# ValdisMCU.net
KiCad netlist of a schematic drawn in Altium Designer
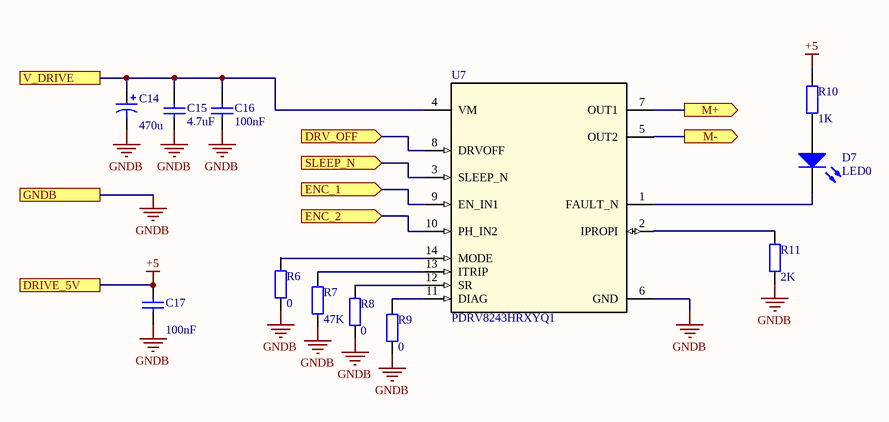
[diagram p0: ValdisMCU.SchDoc]

(export (version "E")
  (design (tool "Eeschema 10.0.6"))
  (components
    (comp (ref "C14")
      (value "470u")
      (footprint "RB7.6-15")
      (description "Polarized Capacitor (Radial)")
      (fields (field (name "Comment") "Cap Pol1") (field (name "PUBLISHER") "Altium Limited"))
      (libsource (lib "Miscellaneous Devices") (part "Cap Pol1"))
    )
    (comp (ref "C15")
      (value "4.7uF")
      (description "Capacitor")
      (libsource (lib "Simulation Generic Components") (part "Capacitor"))
    )
    (comp (ref "C16")
      (value "100nF")
      (description "Capacitor")
      (libsource (lib "Simulation Generic Components") (part "Capacitor"))
    )
    (comp (ref "C17")
      (value "100nF")
      (footprint "RAD-0.3")
      (description "Capacitor")
      (fields (field (name "Comment") "Cap") (field (name "PUBLISHER") "Altium Limited"))
      (libsource (lib "Miscellaneous Devices") (part "Cap"))
    )
    (comp (ref "D7")
      (value "LED0")
      (footprint "LED-0")
      (description "Typical INFRARED GaAs LED")
      (fields (field (name "PUBLISHER") "Altium Limited"))
      (libsource (lib "Miscellaneous Devices") (part "LED0"))
    )
    (comp (ref "R6")
      (value "0")
      (footprint "AXIAL-0.4")
      (description "Resistor")
      (fields (field (name "Comment") "Res2") (field (name "PUBLISHER") "Altium Limited"))
      (libsource (lib "Miscellaneous Devices") (part "Res2"))
    )
    (comp (ref "R7")
      (value "47K")
      (footprint "AXIAL-0.4")
      (description "Resistor")
      (fields (field (name "Comment") "Res2") (field (name "PUBLISHER") "Altium Limited"))
      (libsource (lib "Miscellaneous Devices") (part "Res2"))
    )
    (comp (ref "R8")
      (value "0")
      (footprint "AXIAL-0.4")
      (description "Resistor")
      (fields (field (name "Comment") "Res2") (field (name "PUBLISHER") "Altium Limited"))
      (libsource (lib "") (part "Res2_1"))
    )
    (comp (ref "R9")
      (value "0")
      (footprint "AXIAL-0.4")
      (description "Resistor")
      (fields (field (name "Comment") "Res2") (field (name "PUBLISHER") "Altium Limited"))
      (libsource (lib "Miscellaneous Devices") (part "Res2"))
    )
    (comp (ref "R10")
      (value "1K")
      (footprint "AXIAL-0.4")
      (description "Resistor")
      (fields (field (name "Comment") "Res2") (field (name "PUBLISHER") "Altium Limited"))
      (libsource (lib "Miscellaneous Devices") (part "Res2"))
    )
    (comp (ref "R11")
      (value "2K")
      (footprint "AXIAL-0.4")
      (description "Resistor")
      (fields (field (name "Comment") "Res2") (field (name "PUBLISHER") "Altium Limited"))
      (libsource (lib "Miscellaneous Devices") (part "Res2"))
    )
    (comp (ref "U7")
      (value "PDRV8243HRXYQ1")
      (footprint "RXY0014A-MFG")
      (description "No Description Available")
      (fields (field (name "COPYRIGHT") "Copyright (C) 2022 Ultra Librarian. All rights reserved."))
      (libsource (lib "PDRV8243HRXYQ1") (part "PDRV8243HRXYQ1"))
    )
  )
  (nets
    (net (code "1") (name "+5") (class "Default")
      (node (ref "C17") (pin "2") (pinfunction "2_2") (pintype "passive"))
      (node (ref "R10") (pin "2") (pinfunction "2_2") (pintype "passive"))
    )
    (net (code "2") (name "/DRV_OFF") (class "Default")
      (node (ref "U7") (pin "8") (pinfunction "DRVOFF_8") (pintype "input"))
    )
    (net (code "3") (name "/ENC_1") (class "Default")
      (node (ref "U7") (pin "9") (pinfunction "EN_IN1_9") (pintype "input"))
    )
    (net (code "4") (name "/ENC_2") (class "Default")
      (node (ref "U7") (pin "10") (pinfunction "PH_IN2_10") (pintype "input"))
    )
    (net (code "5") (name "/M+") (class "Default")
      (node (ref "U7") (pin "7") (pinfunction "OUT1_7") (pintype "passive"))
    )
    (net (code "6") (name "/M-") (class "Default")
      (node (ref "U7") (pin "5") (pinfunction "OUT2_5") (pintype "passive"))
    )
    (net (code "7") (name "/SLEEP_N") (class "Default")
      (node (ref "U7") (pin "3") (pinfunction "SLEEP_N_3") (pintype "input"))
    )
    (net (code "8") (name "/V_DRIVE") (class "Default")
      (node (ref "C14") (pin "1") (pinfunction "1_1") (pintype "passive"))
      (node (ref "C15") (pin "2") (pinfunction "2_2") (pintype "passive"))
      (node (ref "C16") (pin "1") (pinfunction "1_1") (pintype "passive"))
      (node (ref "U7") (pin "4") (pinfunction "VM_4") (pintype "power_in"))
    )
    (net (code "9") (name "GNDB") (class "Default")
      (node (ref "C14") (pin "2") (pinfunction "2_2") (pintype "passive"))
      (node (ref "C15") (pin "1") (pinfunction "1_1") (pintype "passive"))
      (node (ref "C16") (pin "2") (pinfunction "2_2") (pintype "passive"))
      (node (ref "C17") (pin "1") (pinfunction "1_1") (pintype "passive"))
      (node (ref "R11") (pin "1") (pinfunction "1_1") (pintype "passive"))
      (node (ref "R6") (pin "1") (pinfunction "1_1") (pintype "passive"))
      (node (ref "R7") (pin "1") (pinfunction "1_1") (pintype "passive"))
      (node (ref "R8") (pin "2") (pinfunction "2_2") (pintype "passive"))
      (node (ref "R9") (pin "1") (pinfunction "1_1") (pintype "passive"))
      (node (ref "U7") (pin "6") (pinfunction "GND_6") (pintype "power_in"))
    )
    (net (code "10") (name "Net-(D7-A)") (class "Default")
      (node (ref "D7") (pin "1") (pinfunction "A_1") (pintype "passive"))
      (node (ref "R10") (pin "1") (pinfunction "1_1") (pintype "passive"))
    )
    (net (code "11") (name "Net-(D7-K)") (class "Default")
      (node (ref "D7") (pin "2") (pinfunction "K_2") (pintype "passive"))
      (node (ref "U7") (pin "1") (pinfunction "FAULT_N_1") (pintype "open_collector"))
    )
    (net (code "12") (name "Net-(U7-DIAG)") (class "Default")
      (node (ref "R9") (pin "2") (pinfunction "2_2") (pintype "passive"))
      (node (ref "U7") (pin "11") (pinfunction "DIAG_11") (pintype "input"))
    )
    (net (code "13") (name "Net-(U7-IPROPI)") (class "Default")
      (node (ref "R11") (pin "2") (pinfunction "2_2") (pintype "passive"))
      (node (ref "U7") (pin "2") (pinfunction "IPROPI_2") (pintype "bidirectional"))
    )
    (net (code "14") (name "Net-(U7-ITRIP)") (class "Default")
      (node (ref "R7") (pin "2") (pinfunction "2_2") (pintype "passive"))
      (node (ref "U7") (pin "13") (pinfunction "ITRIP_13") (pintype "input"))
    )
    (net (code "15") (name "Net-(U7-MODE)") (class "Default")
      (node (ref "R6") (pin "2") (pinfunction "2_2") (pintype "passive"))
      (node (ref "U7") (pin "14") (pinfunction "MODE_14") (pintype "input"))
    )
    (net (code "16") (name "Net-(U7-SR)") (class "Default")
      (node (ref "R8") (pin "1") (pinfunction "1_1") (pintype "passive"))
      (node (ref "U7") (pin "12") (pinfunction "SR_12") (pintype "input"))
    )
  )
)
